# Display.net
KiCad netlist of a schematic drawn in Altium Designer
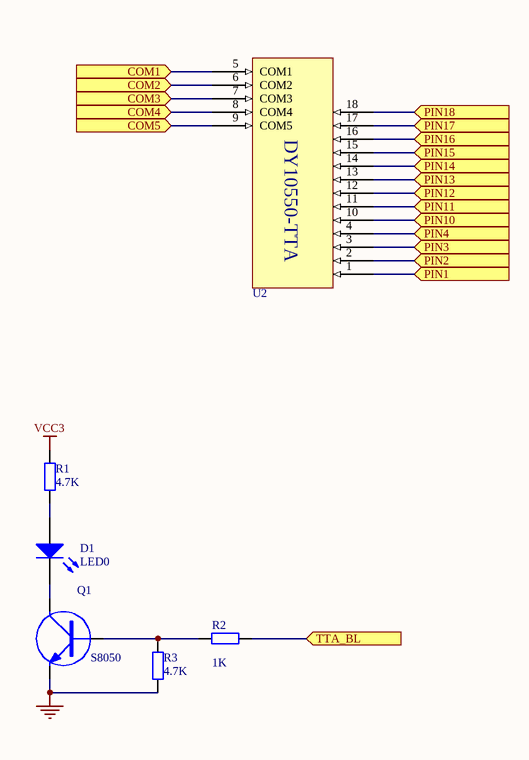
[diagram p0: Display.SchDoc]

(export (version "E")
  (design (tool "Eeschema 10.0.6"))
  (components
    (comp (ref "D1")
      (value "LED0")
      (description "Typical INFRARED GaAs LED")
      (fields (field (name "PUBLISHER") "Altium Limited"))
      (libsource (lib "Miscellaneous Devices") (part "LED0"))
    )
    (comp (ref "Q1") (value "S8050") (description "NPN Transistor") (libsource (lib "*") (part "NPN")))
    (comp (ref "R1")
      (value "4.7K")
      (description "Resistor")
      (fields (field (name "Comment") "Res2") (field (name "PUBLISHER") "Altium Limited"))
      (libsource (lib "") (part "Res2_1"))
    )
    (comp (ref "R2")
      (value "1K")
      (description "Resistor")
      (fields (field (name "Comment") "Res2") (field (name "PUBLISHER") "Altium Limited"))
      (libsource (lib "Miscellaneous Devices") (part "Res2"))
    )
    (comp (ref "R3")
      (value "4.7K")
      (description "Resistor")
      (fields (field (name "Comment") "100K") (field (name "PUBLISHER") "Altium Limited"))
      (libsource (lib "") (part "Res2_1"))
    )
    (comp (ref "U2") (value "DY10550-TTA_1") (libsource (lib "Schlib") (part "DY10550-TTA_1")))
  )
  (nets
    (net (code "1") (name "/COM1") (class "Default")
      (node (ref "U2") (pin "5") (pinfunction "COM1_5") (pintype "input"))
    )
    (net (code "2") (name "/COM2") (class "Default")
      (node (ref "U2") (pin "6") (pinfunction "COM2_6") (pintype "input"))
    )
    (net (code "3") (name "/COM3") (class "Default")
      (node (ref "U2") (pin "7") (pinfunction "COM3_7") (pintype "input"))
    )
    (net (code "4") (name "/COM4") (class "Default")
      (node (ref "U2") (pin "8") (pinfunction "COM4_8") (pintype "input"))
    )
    (net (code "5") (name "/COM5") (class "Default")
      (node (ref "U2") (pin "9") (pinfunction "COM5_9") (pintype "input"))
    )
    (net (code "6") (name "/PIN1") (class "Default") (node (ref "U2") (pin "1") (pintype "input")))
    (net (code "7") (name "/PIN2") (class "Default") (node (ref "U2") (pin "2") (pintype "input")))
    (net (code "8") (name "/PIN3") (class "Default") (node (ref "U2") (pin "3") (pintype "input")))
    (net (code "9") (name "/PIN4") (class "Default") (node (ref "U2") (pin "4") (pintype "input")))
    (net (code "10") (name "/PIN10") (class "Default") (node (ref "U2") (pin "10") (pintype "input")))
    (net (code "11") (name "/PIN11") (class "Default") (node (ref "U2") (pin "11") (pintype "input")))
    (net (code "12") (name "/PIN12") (class "Default") (node (ref "U2") (pin "12") (pintype "input")))
    (net (code "13") (name "/PIN13") (class "Default") (node (ref "U2") (pin "13") (pintype "input")))
    (net (code "14") (name "/PIN14") (class "Default") (node (ref "U2") (pin "14") (pintype "input")))
    (net (code "15") (name "/PIN15") (class "Default") (node (ref "U2") (pin "15") (pintype "input")))
    (net (code "16") (name "/PIN16") (class "Default") (node (ref "U2") (pin "16") (pintype "input")))
    (net (code "17") (name "/PIN17") (class "Default") (node (ref "U2") (pin "17") (pintype "input")))
    (net (code "18") (name "/PIN18") (class "Default") (node (ref "U2") (pin "18") (pintype "input")))
    (net (code "19") (name "/TTA_BL") (class "Default")
      (node (ref "R2") (pin "2") (pinfunction "2_2") (pintype "passive"))
    )
    (net (code "20") (name "GND") (class "Default")
      (node (ref "Q1") (pin "2") (pinfunction "E_2") (pintype "passive"))
      (node (ref "R3") (pin "1") (pinfunction "1_1") (pintype "passive"))
    )
    (net (code "21") (name "Net-(D1-A)") (class "Default")
      (node (ref "D1") (pin "1") (pinfunction "A_1") (pintype "passive"))
      (node (ref "R1") (pin "1") (pinfunction "1_1") (pintype "passive"))
    )
    (net (code "22") (name "Net-(D1-K)") (class "Default")
      (node (ref "D1") (pin "2") (pinfunction "K_2") (pintype "passive"))
      (node (ref "Q1") (pin "3") (pinfunction "C_3") (pintype "passive"))
    )
    (net (code "23") (name "Net-(Q1-B)") (class "Default")
      (node (ref "Q1") (pin "1") (pinfunction "B_1") (pintype "passive"))
      (node (ref "R2") (pin "1") (pinfunction "1_1") (pintype "passive"))
      (node (ref "R3") (pin "2") (pinfunction "2_2") (pintype "passive"))
    )
    (net (code "24") (name "VCC3") (class "Default")
      (node (ref "R1") (pin "2") (pinfunction "2_2") (pintype "passive"))
    )
  )
)
